# receivers1.net
KiCad netlist of a schematic drawn in Altium Designer
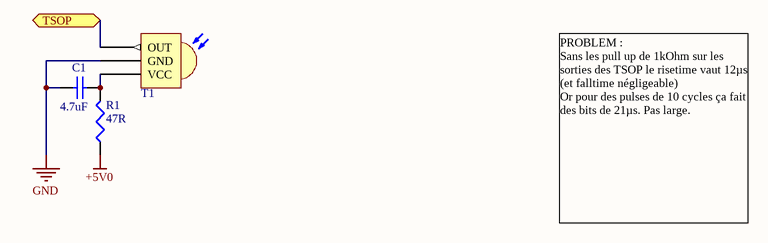
[diagram p0: receivers1.SchDoc]

(export (version "E")
  (design (tool "Eeschema 10.0.6"))
  (components
    (comp (ref "C1")
      (value "4.7uF")
      (footprint "C0805C")
      (description "Capacitor")
      (fields (field (name "Comment") "CAP") (field (name "PUBLISHER") "Altium Limited"))
      (libsource (lib "7Robot") (part "CAP"))
    )
    (comp (ref "R1")
      (value "47R")
      (footprint "C0805R")
      (description "Resistor")
      (fields (field (name "Comment") "RES") (field (name "PUBLISHER") "Altium Limited"))
      (libsource (lib "7Robot") (part "RES"))
    )
    (comp (ref "T1")
      (value "TSOP7000")
      (footprint "TSOP IR")
      (description "Vishay 455kHz IR Receiver")
      (libsource (lib "7Robot") (part "TSOP7000"))
    )
  )
  (nets
    (net (code "1") (name "+5V0") (class "Default")
      (node (ref "R1") (pin "1") (pinfunction "1_1") (pintype "passive"))
    )
    (net (code "2") (name "/TSOP") (class "Default")
      (node (ref "T1") (pin "1") (pinfunction "OUT_1") (pintype "output"))
    )
    (net (code "3") (name "GND") (class "Default")
      (node (ref "C1") (pin "2") (pinfunction "2_2") (pintype "passive"))
      (node (ref "T1") (pin "2") (pinfunction "GND_2") (pintype "power_in"))
    )
    (net (code "4") (name "Net-(T1-VCC)") (class "Default")
      (node (ref "C1") (pin "1") (pinfunction "1_1") (pintype "passive"))
      (node (ref "R1") (pin "2") (pinfunction "2_2") (pintype "passive"))
      (node (ref "T1") (pin "3") (pinfunction "VCC_3") (pintype "power_in"))
    )
  )
)
